# dust_environment_sensor_v3.net
KiCad netlist of a schematic drawn in EAGLE
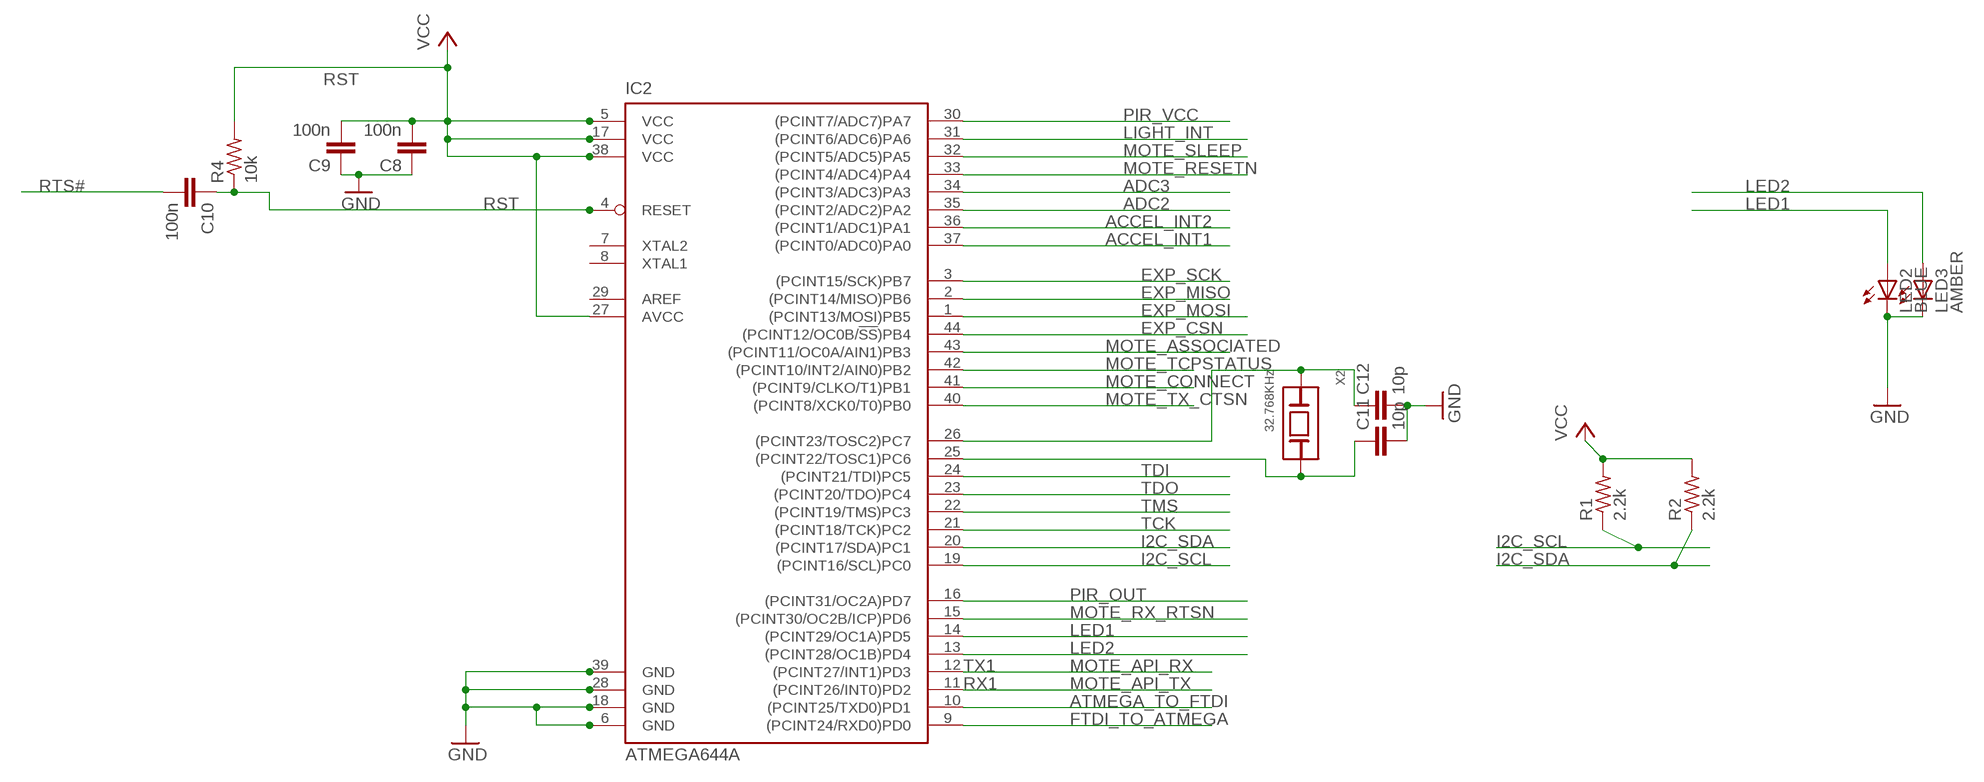
[diagram p0: schematic, sheet 1]
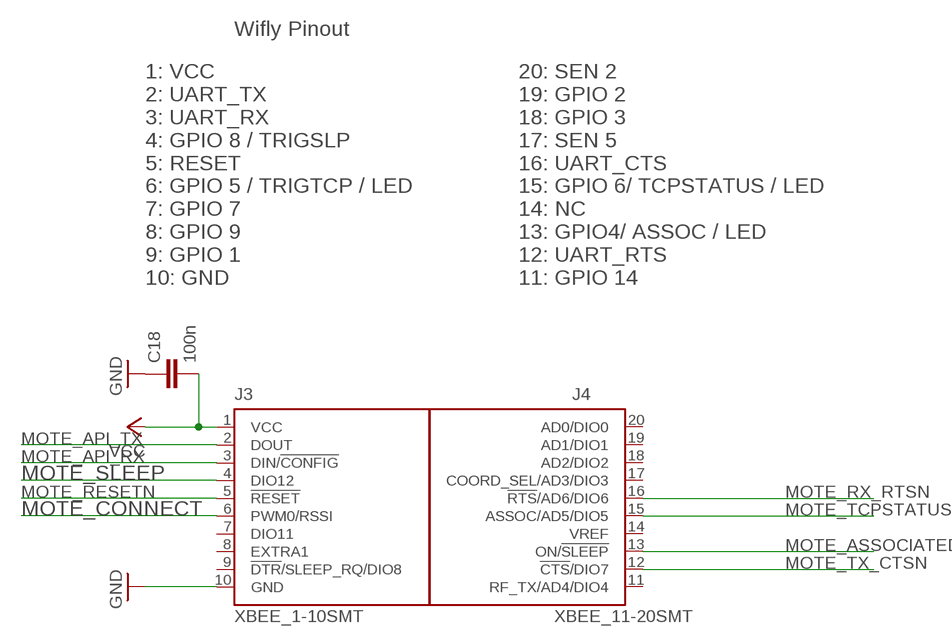
[diagram p1: schematic, sheet 2]
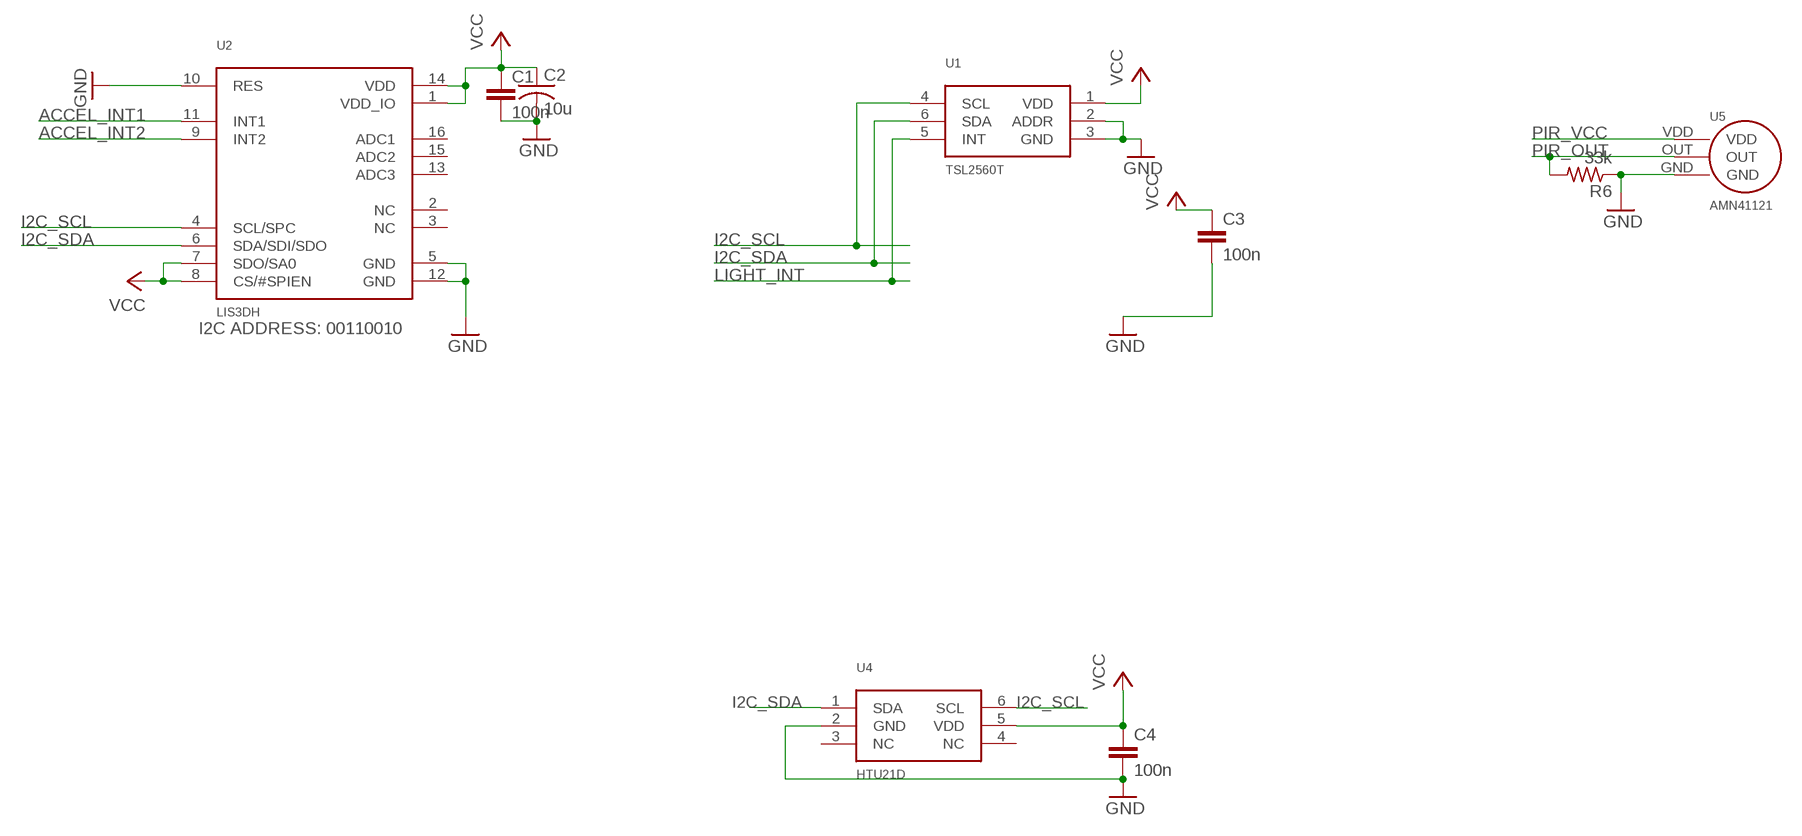
[diagram p2: schematic, sheet 3]
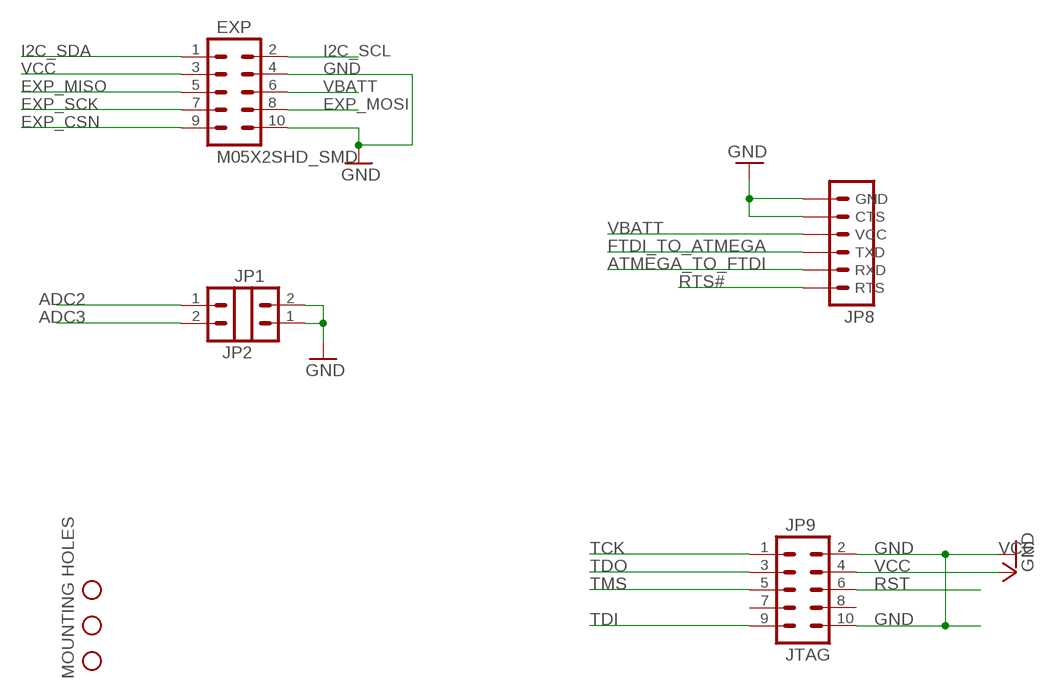
[diagram p3: schematic, sheet 4]
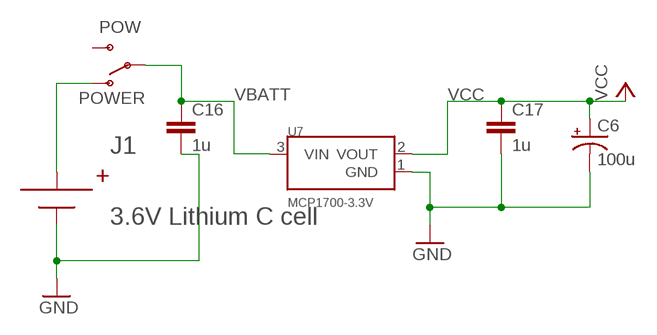
[diagram p4: schematic, sheet 5]

(export (version "E")
  (design (tool "Eeschema 10.0.6"))
  (components
    (comp (ref "C8")
      (value "100n")
      (footprint "eagle-import:C0603")
      (libsource (lib "eagle-import") (part "C-EUC0603"))
    )
    (comp (ref "C9")
      (value "100n")
      (footprint "eagle-import:C0603")
      (libsource (lib "eagle-import") (part "C-EUC0603"))
    )
    (comp (ref "C10")
      (value "100n")
      (footprint "eagle-import:C0603")
      (libsource (lib "eagle-import") (part "C-EUC0603"))
    )
    (comp (ref "C11")
      (value "10p")
      (footprint "eagle-import:C0603")
      (libsource (lib "eagle-import") (part "C-EUC0603"))
    )
    (comp (ref "C12")
      (value "10p")
      (footprint "eagle-import:C0603")
      (libsource (lib "eagle-import") (part "C-EUC0603"))
    )
    (comp (ref "IC2")
      (value "ATMEGA644A")
      (footprint "eagle-import:TQFP44")
      (fields (field (name "MPN") "ATMEGA644PV-10AU"))
      (libsource (lib "eagle-import") (part "ATMEGA644A"))
    )
    (comp (ref "LED2")
      (value "BLUE")
      (footprint "eagle-import:CHIPLED_0805")
      (libsource (lib "eagle-import") (part "LEDCHIPLED_0805"))
    )
    (comp (ref "LED3")
      (value "AMBER")
      (footprint "eagle-import:CHIPLED_0805")
      (libsource (lib "eagle-import") (part "LEDCHIPLED_0805"))
    )
    (comp (ref "R1")
      (value "2.2k")
      (footprint "eagle-import:R0603")
      (libsource (lib "eagle-import") (part "R-US_R0603"))
    )
    (comp (ref "R2")
      (value "2.2k")
      (footprint "eagle-import:R0603")
      (libsource (lib "eagle-import") (part "R-US_R0603"))
    )
    (comp (ref "R4")
      (value "10k")
      (footprint "eagle-import:R0603")
      (libsource (lib "eagle-import") (part "R-US_R0603"))
    )
    (comp (ref "X2")
      (value "32.768KHz")
      (footprint "eagle-import:ABS07")
      (libsource (lib "eagle-import") (part "XTALABS07"))
    )
    (comp (ref "EXP")
      (value "M05X2SHD_SMD")
      (footprint "eagle-import:2X5-SHROUDED_SMD")
      (libsource (lib "eagle-import") (part "M05X2SHD_SMD"))
    )
    (comp (ref "JP1")
      (value "M02PTH")
      (footprint "eagle-import:1X02")
      (libsource (lib "eagle-import") (part "M02PTH"))
    )
    (comp (ref "JP2")
      (value "M02PTH")
      (footprint "eagle-import:1X02")
      (libsource (lib "eagle-import") (part "M02PTH"))
    )
    (comp (ref "JP8")
      (value "FTDI_CABLESIP")
      (footprint "eagle-import:1X06")
      (libsource (lib "eagle-import") (part "FTDI_CABLESIP"))
    )
    (comp (ref "JP9")
      (value "JTAG")
      (footprint "eagle-import:2X5-SHROUDED_SMD")
      (libsource (lib "eagle-import") (part "M05X2SHD_SMD"))
    )
    (comp (ref "STANDOFF1")
      (value "STAND-OFF")
      (footprint "eagle-import:STAND-OFF")
      (libsource (lib "eagle-import") (part "STAND-OFF"))
    )
    (comp (ref "STANDOFF2")
      (value "STAND-OFF")
      (footprint "eagle-import:STAND-OFF")
      (libsource (lib "eagle-import") (part "STAND-OFF"))
    )
    (comp (ref "STANDOFF3")
      (value "STAND-OFF")
      (footprint "eagle-import:STAND-OFF")
      (libsource (lib "eagle-import") (part "STAND-OFF"))
    )
    (comp (ref "C6")
      (value "100u")
      (footprint "eagle-import:EIA7343")
      (libsource (lib "eagle-import") (part "CAP_POL7343"))
    )
    (comp (ref "C16")
      (value "1u")
      (footprint "eagle-import:C0603")
      (libsource (lib "eagle-import") (part "C-EUC0603"))
    )
    (comp (ref "C17")
      (value "1u")
      (footprint "eagle-import:C0603")
      (libsource (lib "eagle-import") (part "C-EUC0603"))
    )
    (comp (ref "J1")
      (value "3.6V Lithium C cell")
      (footprint "eagle-import:BX0036_NOHOLES")
      (libsource (lib "eagle-import") (part "BX0036NH"))
    )
    (comp (ref "POW")
      (value "POWER")
      (footprint "eagle-import:JS102011SAQN")
      (libsource (lib "eagle-import") (part "SWITCH-SPDTSMD3"))
    )
    (comp (ref "U7")
      (value "MCP1700-3.3V")
      (footprint "eagle-import:SOT23-3")
      (libsource (lib "eagle-import") (part "MCP1700"))
    )
    (comp (ref "C18")
      (value "100n")
      (footprint "eagle-import:C0603")
      (libsource (lib "eagle-import") (part "C-EUC0603"))
    )
    (comp (ref "J3")
      (value "XBEE_1-10SMT")
      (footprint "eagle-import:XBEE_1-10_SMT")
      (libsource (lib "eagle-import") (part "XBEE_1-10SMT"))
    )
    (comp (ref "J4")
      (value "XBEE_11-20SMT")
      (footprint "eagle-import:XBEE_11-20_SMT")
      (libsource (lib "eagle-import") (part "XBEE_11-20SMT"))
    )
    (comp (ref "C1")
      (value "100n")
      (footprint "eagle-import:C0603")
      (libsource (lib "eagle-import") (part "C-EUC0603"))
    )
    (comp (ref "C2")
      (value "10u")
      (footprint "eagle-import:C0603")
      (libsource (lib "eagle-import") (part "C-USC0603"))
    )
    (comp (ref "C3")
      (value "100n")
      (footprint "eagle-import:C0603")
      (libsource (lib "eagle-import") (part "C-EUC0603"))
    )
    (comp (ref "C4")
      (value "100n")
      (footprint "eagle-import:C0603")
      (libsource (lib "eagle-import") (part "C-EUC0603"))
    )
    (comp (ref "R6")
      (value "33k")
      (footprint "eagle-import:R0603")
      (libsource (lib "eagle-import") (part "R-US_R0603"))
    )
    (comp (ref "U1")
      (value "TSL2560T")
      (footprint "eagle-import:T_TAOS")
      (libsource (lib "eagle-import") (part "TSL2560T"))
    )
    (comp (ref "U2")
      (value "LIS3DH")
      (footprint "eagle-import:LGA16_ST")
      (libsource (lib "eagle-import") (part "LIS3DH"))
    )
    (comp (ref "U4")
      (value "HTU21D")
      (footprint "eagle-import:HTU21D")
      (libsource (lib "eagle-import") (part "HTU21D"))
    )
    (comp (ref "U5")
      (value "AMN41121")
      (footprint "eagle-import:AMN41121")
      (libsource (lib "eagle-import") (part "AMN41121"))
    )
  )
  (nets
    (net (code "1") (name "ACCEL_INT1") (class "Default")
      (node (ref "IC2") (pin "37") (pinfunction "(PCINT0/ADC0)PA0_37") (pintype "bidirectional"))
      (node (ref "U2") (pin "11") (pinfunction "INT1_11") (pintype "bidirectional"))
    )
    (net (code "2") (name "ACCEL_INT2") (class "Default")
      (node (ref "IC2") (pin "36") (pinfunction "(PCINT1/ADC1)PA1_36") (pintype "bidirectional"))
      (node (ref "U2") (pin "9") (pinfunction "INT2_9") (pintype "bidirectional"))
    )
    (net (code "3") (name "ADC2") (class "Default")
      (node (ref "IC2") (pin "35") (pinfunction "(PCINT2/ADC2)PA2_35") (pintype "bidirectional"))
      (node (ref "JP2") (pin "1") (pinfunction "1_1") (pintype "passive"))
    )
    (net (code "4") (name "ADC3") (class "Default")
      (node (ref "IC2") (pin "34") (pinfunction "(PCINT3/ADC3)PA3_34") (pintype "bidirectional"))
      (node (ref "JP2") (pin "2") (pinfunction "2_2") (pintype "passive"))
    )
    (net (code "5") (name "ATMEGA_TO_FTDI") (class "Default")
      (node (ref "IC2") (pin "10") (pinfunction "(PCINT25/TXD0)PD1_10") (pintype "bidirectional"))
      (node (ref "JP8") (pin "5") (pinfunction "RXD_5") (pintype "passive"))
    )
    (net (code "6") (name "EXP_CSN") (class "Default")
      (node (ref "EXP") (pin "9") (pinfunction "9_9") (pintype "passive"))
      (node (ref "IC2") (pin "44") (pinfunction "(PCINT12/OC0B/~{SS})PB4_44") (pintype "bidirectional"))
    )
    (net (code "7") (name "EXP_MISO") (class "Default")
      (node (ref "EXP") (pin "5") (pinfunction "5_5") (pintype "passive"))
      (node (ref "IC2") (pin "2") (pinfunction "(PCINT14/MISO)PB6_2") (pintype "bidirectional"))
    )
    (net (code "8") (name "EXP_MOSI") (class "Default")
      (node (ref "EXP") (pin "8") (pinfunction "8_8") (pintype "passive"))
      (node (ref "IC2") (pin "1") (pinfunction "(PCINT13/MOSI)PB5_1") (pintype "bidirectional"))
    )
    (net (code "9") (name "EXP_SCK") (class "Default")
      (node (ref "EXP") (pin "7") (pinfunction "7_7") (pintype "passive"))
      (node (ref "IC2") (pin "3") (pinfunction "(PCINT15/SCK)PB7_3") (pintype "bidirectional"))
    )
    (net (code "10") (name "FTDI_TO_ATMEGA") (class "Default")
      (node (ref "IC2") (pin "9") (pinfunction "(PCINT24/RXD0)PD0_9") (pintype "bidirectional"))
      (node (ref "JP8") (pin "4") (pinfunction "TXD_4") (pintype "passive"))
    )
    (net (code "11") (name "GND") (class "Default")
      (node (ref "C1") (pin "2") (pinfunction "2_2") (pintype "passive"))
      (node (ref "C11") (pin "2") (pinfunction "2_2") (pintype "passive"))
      (node (ref "C12") (pin "2") (pinfunction "2_2") (pintype "passive"))
      (node (ref "C16") (pin "2") (pinfunction "2_2") (pintype "passive"))
      (node (ref "C17") (pin "2") (pinfunction "2_2") (pintype "passive"))
      (node (ref "C18") (pin "1") (pinfunction "1_1") (pintype "passive"))
      (node (ref "C2") (pin "2") (pinfunction "2_2") (pintype "passive"))
      (node (ref "C3") (pin "2") (pinfunction "2_2") (pintype "passive"))
      (node (ref "C4") (pin "2") (pinfunction "2_2") (pintype "passive"))
      (node (ref "C6") (pin "C") (pinfunction "-_C") (pintype "passive"))
      (node (ref "C8") (pin "1") (pinfunction "1_1") (pintype "passive"))
      (node (ref "C9") (pin "1") (pinfunction "1_1") (pintype "passive"))
      (node (ref "EXP") (pin "10") (pinfunction "10_10") (pintype "passive"))
      (node (ref "EXP") (pin "4") (pinfunction "4_4") (pintype "passive"))
      (node (ref "IC2") (pin "18") (pinfunction "GND_18") (pintype "power_in"))
      (node (ref "IC2") (pin "28") (pinfunction "GND_28") (pintype "power_in"))
      (node (ref "IC2") (pin "39") (pinfunction "GND_39") (pintype "power_in"))
      (node (ref "IC2") (pin "6") (pinfunction "GND_6") (pintype "power_in"))
      (node (ref "J1") (pin "NEG") (pinfunction "NEG_NEG") (pintype "bidirectional"))
      (node (ref "J3") (pin "10") (pinfunction "GND_10") (pintype "power_in"))
      (node (ref "JP1") (pin "1") (pinfunction "1_1") (pintype "passive"))
      (node (ref "JP1") (pin "2") (pinfunction "2_2") (pintype "passive"))
      (node (ref "JP8") (pin "1") (pinfunction "GND_1") (pintype "passive"))
      (node (ref "JP8") (pin "2") (pinfunction "CTS_2") (pintype "passive"))
      (node (ref "JP9") (pin "10") (pinfunction "10_10") (pintype "passive"))
      (node (ref "JP9") (pin "2") (pinfunction "2_2") (pintype "passive"))
      (node (ref "LED2") (pin "C") (pinfunction "C_C") (pintype "passive"))
      (node (ref "LED3") (pin "C") (pinfunction "C_C") (pintype "passive"))
      (node (ref "R6") (pin "1") (pinfunction "1_1") (pintype "passive"))
      (node (ref "U1") (pin "2") (pinfunction "ADDR_2") (pintype "bidirectional"))
      (node (ref "U1") (pin "3") (pinfunction "GND_3") (pintype "bidirectional"))
      (node (ref "U2") (pin "10") (pinfunction "RES_10") (pintype "bidirectional"))
      (node (ref "U2") (pin "12") (pinfunction "GND_12") (pintype "bidirectional"))
      (node (ref "U2") (pin "5") (pinfunction "GND_5") (pintype "bidirectional"))
      (node (ref "U4") (pin "2") (pinfunction "GND_2") (pintype "bidirectional"))
      (node (ref "U5") (pin "GND") (pinfunction "GND_GND") (pintype "bidirectional"))
      (node (ref "U7") (pin "1") (pinfunction "GND_1") (pintype "bidirectional"))
    )
    (net (code "12") (name "I2C_SCL") (class "Default")
      (node (ref "EXP") (pin "2") (pinfunction "2_2") (pintype "passive"))
      (node (ref "IC2") (pin "19") (pinfunction "(PCINT16/SCL)PC0_19") (pintype "output"))
      (node (ref "R1") (pin "1") (pinfunction "1_1") (pintype "passive"))
      (node (ref "U1") (pin "4") (pinfunction "SCL_4") (pintype "bidirectional"))
      (node (ref "U2") (pin "4") (pinfunction "SCL/SPC_4") (pintype "bidirectional"))
      (node (ref "U4") (pin "6") (pinfunction "SCL_6") (pintype "bidirectional"))
    )
    (net (code "13") (name "I2C_SDA") (class "Default")
      (node (ref "EXP") (pin "1") (pinfunction "1_1") (pintype "passive"))
      (node (ref "IC2") (pin "20") (pinfunction "(PCINT17/SDA)PC1_20") (pintype "output"))
      (node (ref "R2") (pin "1") (pinfunction "1_1") (pintype "passive"))
      (node (ref "U1") (pin "6") (pinfunction "SDA_6") (pintype "bidirectional"))
      (node (ref "U2") (pin "6") (pinfunction "SDA/SDI/SDO_6") (pintype "bidirectional"))
      (node (ref "U4") (pin "1") (pinfunction "SDA_1") (pintype "bidirectional"))
    )
    (net (code "14") (name "LED1") (class "Default")
      (node (ref "IC2") (pin "14") (pinfunction "(PCINT29/OC1A)PD5_14") (pintype "bidirectional"))
      (node (ref "LED2") (pin "A") (pinfunction "A_A") (pintype "passive"))
    )
    (net (code "15") (name "LED2") (class "Default")
      (node (ref "IC2") (pin "13") (pinfunction "(PCINT28/OC1B)PD4_13") (pintype "bidirectional"))
      (node (ref "LED3") (pin "A") (pinfunction "A_A") (pintype "passive"))
    )
    (net (code "16") (name "LIGHT_INT") (class "Default")
      (node (ref "IC2") (pin "31") (pinfunction "(PCINT6/ADC6)PA6_31") (pintype "bidirectional"))
      (node (ref "U1") (pin "5") (pinfunction "INT_5") (pintype "bidirectional"))
    )
    (net (code "17") (name "MOTE_API_RX") (class "Default")
      (node (ref "IC2") (pin "12") (pinfunction "(PCINT27/INT1)PD3_12") (pintype "bidirectional"))
      (node (ref "J3") (pin "3") (pinfunction "DIN/~{CONFIG}_3") (pintype "input"))
    )
    (net (code "18") (name "MOTE_API_TX") (class "Default")
      (node (ref "IC2") (pin "11") (pinfunction "(PCINT26/INT0)PD2_11") (pintype "bidirectional"))
      (node (ref "J3") (pin "2") (pinfunction "DOUT_2") (pintype "output"))
    )
    (net (code "19") (name "MOTE_ASSOCIATED") (class "Default")
      (node (ref "IC2") (pin "43") (pinfunction "(PCINT11/OC0A/AIN1)PB3_43") (pintype "bidirectional"))
      (node (ref "J4") (pin "13") (pinfunction "ON/~{SLEEP}_13") (pintype "output"))
    )
    (net (code "20") (name "MOTE_CONNECT") (class "Default")
      (node (ref "IC2") (pin "41") (pinfunction "(PCINT9/CLKO/T1)PB1_41") (pintype "bidirectional"))
      (node (ref "J3") (pin "6") (pinfunction "PWM0/RSSI_6") (pintype "output"))
    )
    (net (code "21") (name "MOTE_RESETN") (class "Default")
      (node (ref "IC2") (pin "33") (pinfunction "(PCINT4/ADC4)PA4_33") (pintype "bidirectional"))
      (node (ref "J3") (pin "5") (pinfunction "~{RESET}_5") (pintype "input"))
    )
    (net (code "22") (name "MOTE_RX_RTSN") (class "Default")
      (node (ref "IC2") (pin "15") (pinfunction "(PCINT30/OC2B/ICP)PD6_15") (pintype "bidirectional"))
      (node (ref "J4") (pin "16") (pinfunction "~{RTS}/AD6/DIO6_16") (pintype "bidirectional"))
    )
    (net (code "23") (name "MOTE_SLEEP") (class "Default")
      (node (ref "IC2") (pin "32") (pinfunction "(PCINT5/ADC5)PA5_32") (pintype "bidirectional"))
      (node (ref "J3") (pin "4") (pinfunction "DIO12_4") (pintype "bidirectional"))
    )
    (net (code "24") (name "MOTE_TCPSTATUS") (class "Default")
      (node (ref "IC2") (pin "42") (pinfunction "(PCINT10/INT2/AIN0)PB2_42") (pintype "bidirectional"))
      (node (ref "J4") (pin "15") (pinfunction "ASSOC/AD5/DIO5_15") (pintype "bidirectional"))
    )
    (net (code "25") (name "MOTE_TX_CTSN") (class "Default")
      (node (ref "IC2") (pin "40") (pinfunction "(PCINT8/XCK0/T0)PB0_40") (pintype "bidirectional"))
      (node (ref "J4") (pin "12") (pinfunction "~{CTS}/DIO7_12") (pintype "bidirectional"))
    )
    (net (code "26") (name "Net-(IC2-(PCINT22{slash}TOSC1)PC6)") (class "Default")
      (node (ref "C11") (pin "1") (pinfunction "1_1") (pintype "passive"))
      (node (ref "IC2") (pin "25") (pinfunction "(PCINT22/TOSC1)PC6_25") (pintype "output"))
      (node (ref "X2") (pin "2") (pinfunction "B_2") (pintype "bidirectional"))
    )
    (net (code "27") (name "Net-(IC2-(PCINT23{slash}TOSC2)PC7)") (class "Default")
      (node (ref "C12") (pin "1") (pinfunction "1_1") (pintype "passive"))
      (node (ref "IC2") (pin "26") (pinfunction "(PCINT23/TOSC2)PC7_26") (pintype "output"))
      (node (ref "X2") (pin "1") (pinfunction "A_1") (pintype "bidirectional"))
    )
    (net (code "28") (name "Net-(POW-O)") (class "Default")
      (node (ref "J1") (pin "POS") (pinfunction "POS_POS") (pintype "bidirectional"))
      (node (ref "POW") (pin "1") (pinfunction "O_1") (pintype "passive"))
    )
    (net (code "29") (name "PIR_OUT") (class "Default")
      (node (ref "IC2") (pin "16") (pinfunction "(PCINT31/OC2A)PD7_16") (pintype "bidirectional"))
      (node (ref "R6") (pin "2") (pinfunction "2_2") (pintype "passive"))
      (node (ref "U5") (pin "OUT") (pinfunction "OUT_OUT") (pintype "bidirectional"))
    )
    (net (code "30") (name "PIR_VCC") (class "Default")
      (node (ref "IC2") (pin "30") (pinfunction "(PCINT7/ADC7)PA7_30") (pintype "bidirectional"))
      (node (ref "U5") (pin "VDD") (pinfunction "VDD_VDD") (pintype "bidirectional"))
    )
    (net (code "31") (name "RST") (class "Default")
      (node (ref "C10") (pin "1") (pinfunction "1_1") (pintype "passive"))
      (node (ref "IC2") (pin "4") (pinfunction "RESET_4") (pintype "input"))
      (node (ref "JP9") (pin "6") (pinfunction "6_6") (pintype "passive"))
      (node (ref "R4") (pin "1") (pinfunction "1_1") (pintype "passive"))
    )
    (net (code "32") (name "RTS#") (class "Default")
      (node (ref "C10") (pin "2") (pinfunction "2_2") (pintype "passive"))
      (node (ref "JP8") (pin "6") (pinfunction "RTS_6") (pintype "passive"))
    )
    (net (code "33") (name "TCK") (class "Default")
      (node (ref "IC2") (pin "21") (pinfunction "(PCINT18/TCK)PC2_21") (pintype "output"))
      (node (ref "JP9") (pin "1") (pinfunction "1_1") (pintype "passive"))
    )
    (net (code "34") (name "TDI") (class "Default")
      (node (ref "IC2") (pin "24") (pinfunction "(PCINT21/TDI)PC5_24") (pintype "output"))
      (node (ref "JP9") (pin "9") (pinfunction "9_9") (pintype "passive"))
    )
    (net (code "35") (name "TDO") (class "Default")
      (node (ref "IC2") (pin "23") (pinfunction "(PCINT20/TDO)PC4_23") (pintype "output"))
      (node (ref "JP9") (pin "3") (pinfunction "3_3") (pintype "passive"))
    )
    (net (code "36") (name "TMS") (class "Default")
      (node (ref "IC2") (pin "22") (pinfunction "(PCINT19/TMS)PC3_22") (pintype "output"))
      (node (ref "JP9") (pin "5") (pinfunction "5_5") (pintype "passive"))
    )
    (net (code "37") (name "VBATT") (class "Default")
      (node (ref "C16") (pin "1") (pinfunction "1_1") (pintype "passive"))
      (node (ref "EXP") (pin "6") (pinfunction "6_6") (pintype "passive"))
      (node (ref "JP8") (pin "3") (pinfunction "VCC_3") (pintype "passive"))
      (node (ref "POW") (pin "C") (pinfunction "P_C") (pintype "passive"))
      (node (ref "U7") (pin "3") (pinfunction "VIN_3") (pintype "bidirectional"))
    )
    (net (code "38") (name "VCC") (class "Default")
      (node (ref "C1") (pin "1") (pinfunction "1_1") (pintype "passive"))
      (node (ref "C17") (pin "1") (pinfunction "1_1") (pintype "passive"))
      (node (ref "C18") (pin "2") (pinfunction "2_2") (pintype "passive"))
      (node (ref "C2") (pin "1") (pinfunction "1_1") (pintype "passive"))
      (node (ref "C3") (pin "1") (pinfunction "1_1") (pintype "passive"))
      (node (ref "C4") (pin "1") (pinfunction "1_1") (pintype "passive"))
      (node (ref "C6") (pin "A") (pinfunction "+_A") (pintype "passive"))
      (node (ref "C8") (pin "2") (pinfunction "2_2") (pintype "passive"))
      (node (ref "C9") (pin "2") (pinfunction "2_2") (pintype "passive"))
      (node (ref "EXP") (pin "3") (pinfunction "3_3") (pintype "passive"))
      (node (ref "IC2") (pin "17") (pinfunction "VCC_17") (pintype "power_in"))
      (node (ref "IC2") (pin "27") (pinfunction "AVCC_27") (pintype "power_in"))
      (node (ref "IC2") (pin "38") (pinfunction "VCC_38") (pintype "power_in"))
      (node (ref "IC2") (pin "5") (pinfunction "VCC_5") (pintype "power_in"))
      (node (ref "J3") (pin "1") (pinfunction "VCC_1") (pintype "power_in"))
      (node (ref "JP9") (pin "4") (pinfunction "4_4") (pintype "passive"))
      (node (ref "R1") (pin "2") (pinfunction "2_2") (pintype "passive"))
      (node (ref "R2") (pin "2") (pinfunction "2_2") (pintype "passive"))
      (node (ref "R4") (pin "2") (pinfunction "2_2") (pintype "passive"))
      (node (ref "U1") (pin "1") (pinfunction "VDD_1") (pintype "bidirectional"))
      (node (ref "U2") (pin "1") (pinfunction "VDD_IO_1") (pintype "bidirectional"))
      (node (ref "U2") (pin "14") (pinfunction "VDD_14") (pintype "bidirectional"))
      (node (ref "U2") (pin "7") (pinfunction "SDO/SA0_7") (pintype "bidirectional"))
      (node (ref "U2") (pin "8") (pinfunction "CS/#SPIEN_8") (pintype "bidirectional"))
      (node (ref "U4") (pin "5") (pinfunction "VDD_5") (pintype "bidirectional"))
      (node (ref "U7") (pin "2") (pinfunction "VOUT_2") (pintype "bidirectional"))
    )
    (net (code "39") (name "unconnected-(IC2-AREF-Pad29)") (class "Default")
      (node (ref "IC2") (pin "29") (pinfunction "AREF_29") (pintype "passive"))
    )
    (net (code "40") (name "unconnected-(IC2-XTAL1-Pad8)") (class "Default")
      (node (ref "IC2") (pin "8") (pinfunction "XTAL1_8") (pintype "bidirectional"))
    )
    (net (code "41") (name "unconnected-(IC2-XTAL2-Pad7)") (class "Default")
      (node (ref "IC2") (pin "7") (pinfunction "XTAL2_7") (pintype "bidirectional"))
    )
    (net (code "42") (name "unconnected-(J3-DIO11-Pad7)") (class "Default")
      (node (ref "J3") (pin "7") (pinfunction "DIO11_7") (pintype "output"))
    )
    (net (code "43") (name "unconnected-(J3-EXTRA1-Pad8)") (class "Default")
      (node (ref "J3") (pin "8") (pinfunction "EXTRA1_8") (pintype "bidirectional"))
    )
    (net (code "44") (name "unconnected-(J3-~{DTR}{slash}SLEEP_RQ{slash}DIO8-Pad9)") (class "Default")
      (node (ref "J3") (pin "9") (pinfunction "~{DTR}/SLEEP_RQ/DIO8_9") (pintype "bidirectional"))
    )
    (net (code "45") (name "unconnected-(J4-AD0{slash}DIO0-Pad20)") (class "Default")
      (node (ref "J4") (pin "20") (pinfunction "AD0/DIO0_20") (pintype "bidirectional"))
    )
    (net (code "46") (name "unconnected-(J4-AD1{slash}DIO1-Pad19)") (class "Default")
      (node (ref "J4") (pin "19") (pinfunction "AD1/DIO1_19") (pintype "bidirectional"))
    )
    (net (code "47") (name "unconnected-(J4-AD2{slash}DIO2-Pad18)") (class "Default")
      (node (ref "J4") (pin "18") (pinfunction "AD2/DIO2_18") (pintype "bidirectional"))
    )
    (net (code "48") (name "unconnected-(J4-COORD_SEL{slash}AD3{slash}DIO3-Pad17)") (class "Default")
      (node (ref "J4") (pin "17") (pinfunction "COORD_SEL/AD3/DIO3_17") (pintype "bidirectional"))
    )
    (net (code "49") (name "unconnected-(J4-RF_TX{slash}AD4{slash}DIO4-Pad11)") (class "Default")
      (node (ref "J4") (pin "11") (pinfunction "RF_TX/AD4/DIO4_11") (pintype "bidirectional"))
    )
    (net (code "50") (name "unconnected-(J4-VREF-Pad14)") (class "Default")
      (node (ref "J4") (pin "14") (pinfunction "VREF_14") (pintype "input"))
    )
    (net (code "51") (name "unconnected-(JP9-Pad7)") (class "Default")
      (node (ref "JP9") (pin "7") (pinfunction "7_7") (pintype "passive"))
    )
    (net (code "52") (name "unconnected-(JP9-Pad8)") (class "Default")
      (node (ref "JP9") (pin "8") (pinfunction "8_8") (pintype "passive"))
    )
    (net (code "53") (name "unconnected-(POW-S-Pad2)") (class "Default")
      (node (ref "POW") (pin "2") (pinfunction "S_2") (pintype "passive"))
    )
    (net (code "54") (name "unconnected-(U2-ADC1-Pad16)") (class "Default")
      (node (ref "U2") (pin "16") (pinfunction "ADC1_16") (pintype "bidirectional"))
    )
    (net (code "55") (name "unconnected-(U2-ADC2-Pad15)") (class "Default")
      (node (ref "U2") (pin "15") (pinfunction "ADC2_15") (pintype "bidirectional"))
    )
    (net (code "56") (name "unconnected-(U2-ADC3-Pad13)") (class "Default")
      (node (ref "U2") (pin "13") (pinfunction "ADC3_13") (pintype "bidirectional"))
    )
    (net (code "57") (name "unconnected-(U2-NC-Pad2)") (class "Default")
      (node (ref "U2") (pin "2") (pinfunction "NC_2") (pintype "bidirectional"))
    )
    (net (code "58") (name "unconnected-(U2-NC-Pad3)") (class "Default")
      (node (ref "U2") (pin "3") (pinfunction "NC_3") (pintype "bidirectional"))
    )
    (net (code "59") (name "unconnected-(U4-NC-Pad3)") (class "Default")
      (node (ref "U4") (pin "3") (pinfunction "NC_3") (pintype "bidirectional"))
    )
    (net (code "60") (name "unconnected-(U4-NC-Pad4)") (class "Default")
      (node (ref "U4") (pin "4") (pinfunction "NC_4") (pintype "bidirectional"))
    )
  )
)
